# martice_relais.net
KiCad netlist of a schematic drawn in Altium Designer
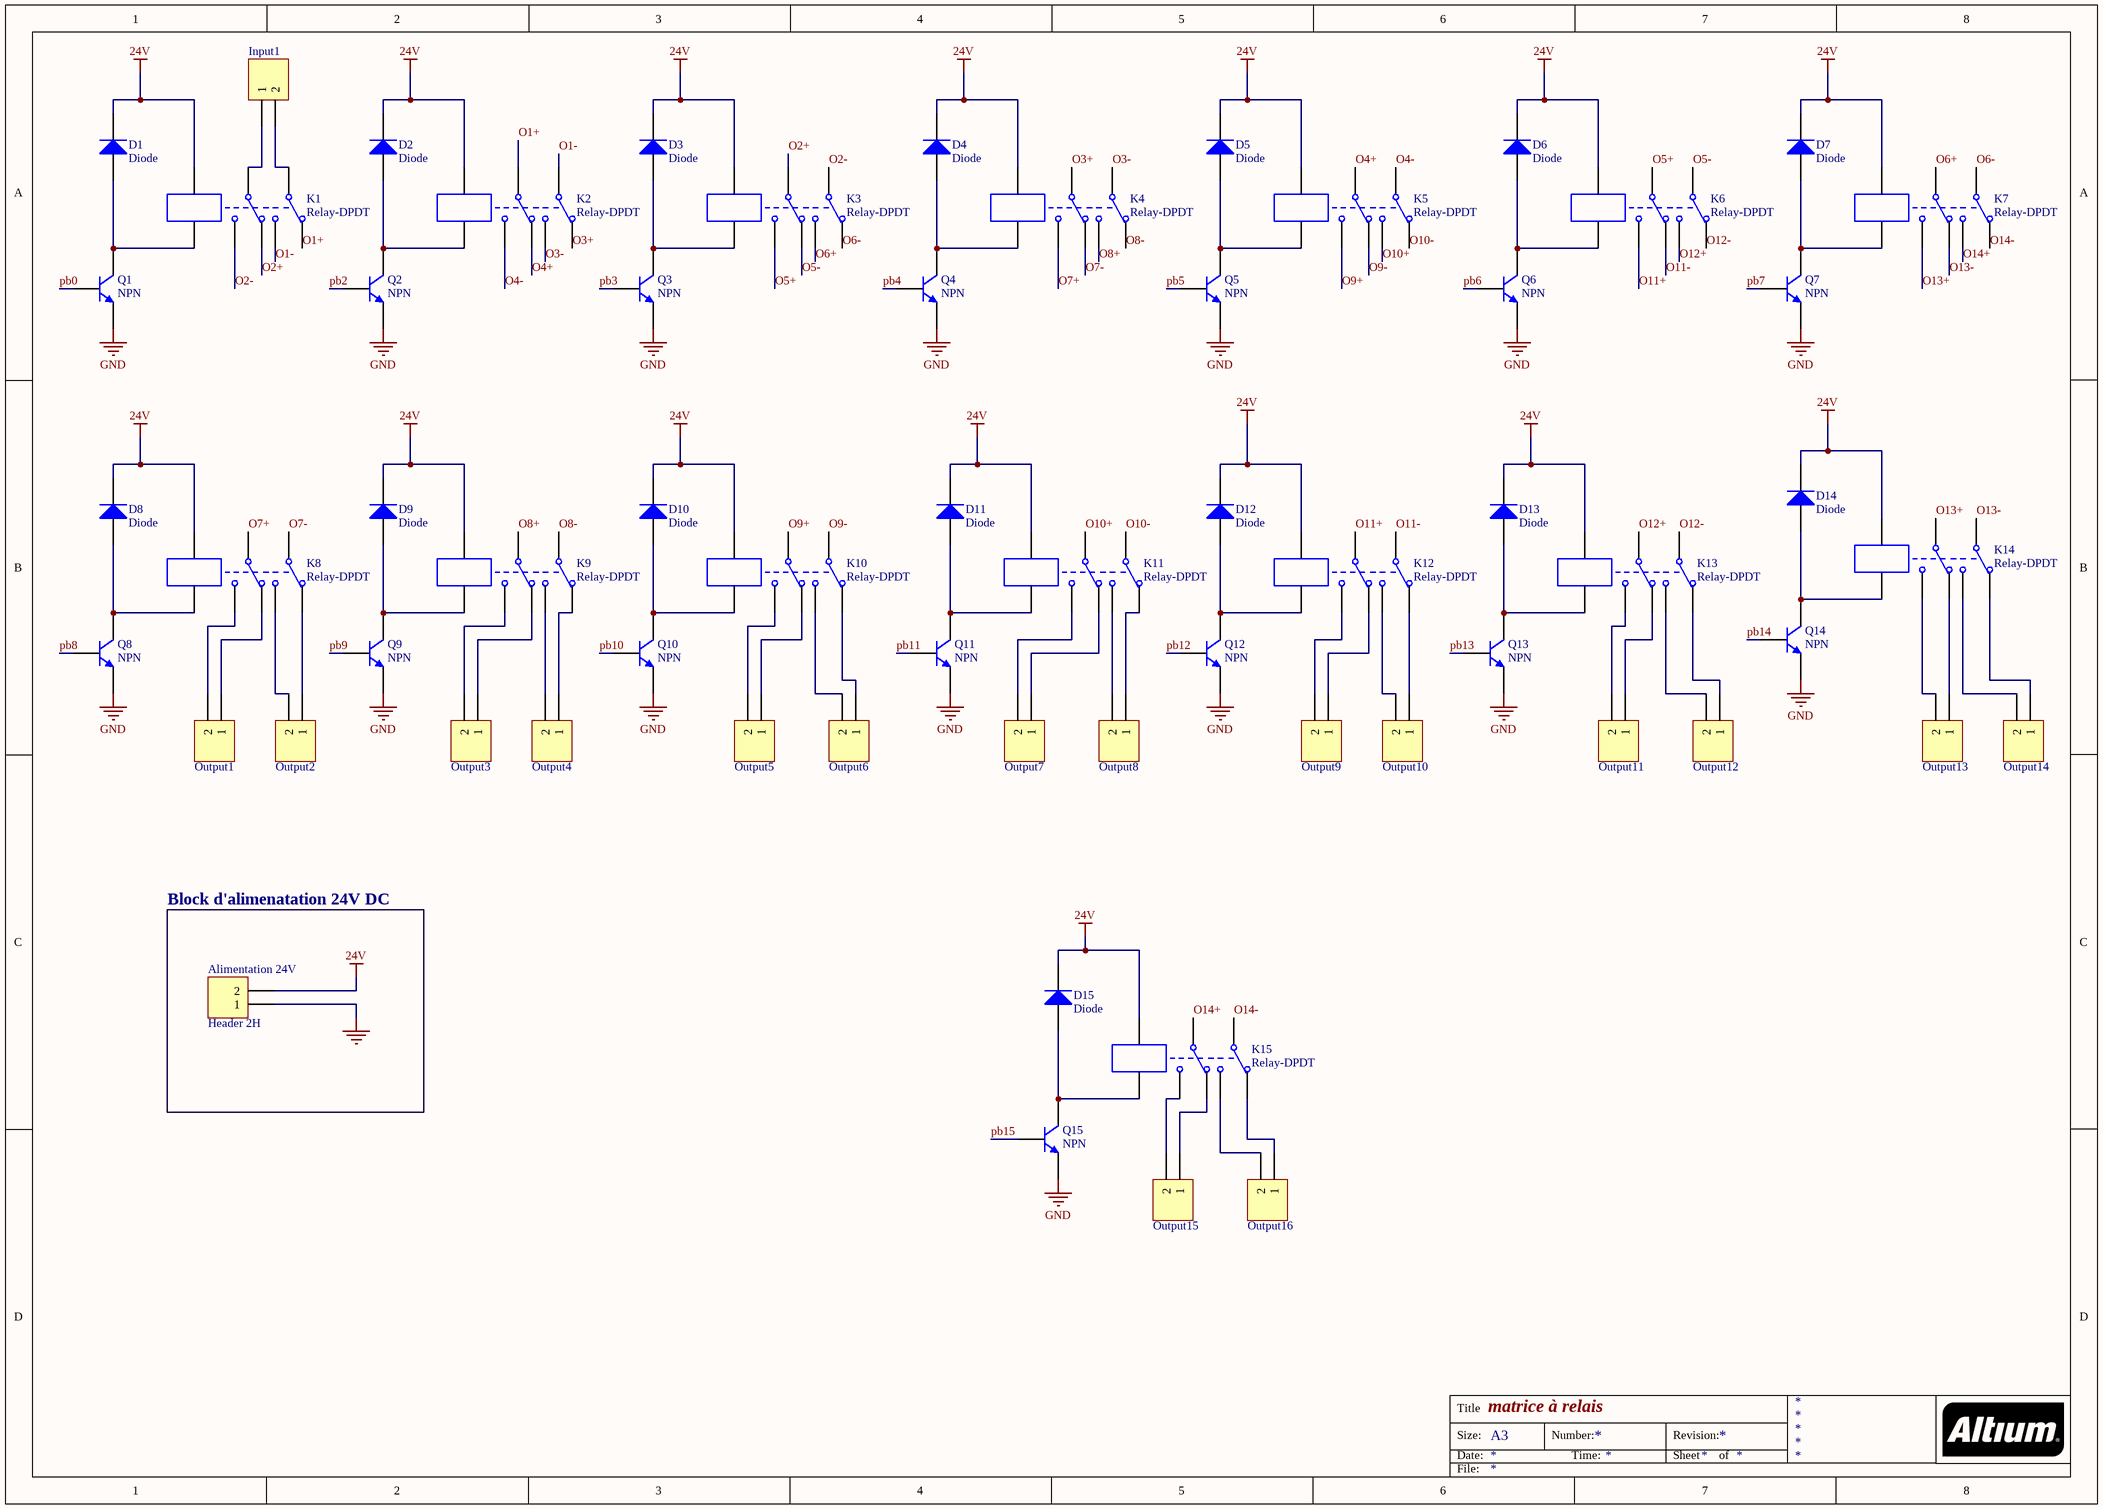
[diagram p0: martice_relais.SchDoc]

(export (version "E")
  (design (tool "Eeschema 10.0.6"))
  (components
    (comp (ref "Alimentation 24V")
      (value "Header 2H")
      (footprint "HDR1X2H")
      (description "Header, 2-Pin, Right Angle")
      (fields (field (name "PUBLISHER") "Altium Limited"))
      (libsource (lib "") (part "Header 2H_2"))
    )
    (comp (ref "D1")
      (value "Diode")
      (footprint "SMC")
      (description "Default Diode")
      (fields (field (name "PUBLISHER") "Altium Limited"))
      (libsource (lib "Miscellaneous Devices") (part "Diode"))
    )
    (comp (ref "D2")
      (value "Diode")
      (footprint "SMC")
      (description "Default Diode")
      (fields (field (name "PUBLISHER") "Altium Limited"))
      (libsource (lib "Miscellaneous Devices") (part "Diode"))
    )
    (comp (ref "D3")
      (value "Diode")
      (footprint "SMC")
      (description "Default Diode")
      (fields (field (name "PUBLISHER") "Altium Limited"))
      (libsource (lib "Miscellaneous Devices") (part "Diode"))
    )
    (comp (ref "D4")
      (value "Diode")
      (footprint "SMC")
      (description "Default Diode")
      (fields (field (name "PUBLISHER") "Altium Limited"))
      (libsource (lib "Miscellaneous Devices") (part "Diode"))
    )
    (comp (ref "D5")
      (value "Diode")
      (footprint "SMC")
      (description "Default Diode")
      (fields (field (name "PUBLISHER") "Altium Limited"))
      (libsource (lib "Miscellaneous Devices") (part "Diode"))
    )
    (comp (ref "D6")
      (value "Diode")
      (footprint "SMC")
      (description "Default Diode")
      (fields (field (name "PUBLISHER") "Altium Limited"))
      (libsource (lib "Miscellaneous Devices") (part "Diode"))
    )
    (comp (ref "D7")
      (value "Diode")
      (footprint "SMC")
      (description "Default Diode")
      (fields (field (name "PUBLISHER") "Altium Limited"))
      (libsource (lib "Miscellaneous Devices") (part "Diode"))
    )
    (comp (ref "D8")
      (value "Diode")
      (footprint "SMC")
      (description "Default Diode")
      (fields (field (name "PUBLISHER") "Altium Limited"))
      (libsource (lib "Miscellaneous Devices") (part "Diode"))
    )
    (comp (ref "D9")
      (value "Diode")
      (footprint "SMC")
      (description "Default Diode")
      (fields (field (name "PUBLISHER") "Altium Limited"))
      (libsource (lib "Miscellaneous Devices") (part "Diode"))
    )
    (comp (ref "D10")
      (value "Diode")
      (footprint "SMC")
      (description "Default Diode")
      (fields (field (name "PUBLISHER") "Altium Limited"))
      (libsource (lib "Miscellaneous Devices") (part "Diode"))
    )
    (comp (ref "D11")
      (value "Diode")
      (footprint "SMC")
      (description "Default Diode")
      (fields (field (name "PUBLISHER") "Altium Limited"))
      (libsource (lib "Miscellaneous Devices") (part "Diode"))
    )
    (comp (ref "D12")
      (value "Diode")
      (footprint "SMC")
      (description "Default Diode")
      (fields (field (name "PUBLISHER") "Altium Limited"))
      (libsource (lib "Miscellaneous Devices") (part "Diode"))
    )
    (comp (ref "D13")
      (value "Diode")
      (footprint "SMC")
      (description "Default Diode")
      (fields (field (name "PUBLISHER") "Altium Limited"))
      (libsource (lib "Miscellaneous Devices") (part "Diode"))
    )
    (comp (ref "D14")
      (value "Diode")
      (footprint "SMC")
      (description "Default Diode")
      (fields (field (name "PUBLISHER") "Altium Limited"))
      (libsource (lib "Miscellaneous Devices") (part "Diode"))
    )
    (comp (ref "D15")
      (value "Diode")
      (footprint "SMC")
      (description "Default Diode")
      (fields (field (name "PUBLISHER") "Altium Limited"))
      (libsource (lib "Miscellaneous Devices") (part "Diode"))
    )
    (comp (ref "Input1")
      (value "Header 2H")
      (footprint "HDR1X2H")
      (description "Header, 2-Pin, Right Angle")
      (fields (field (name "PUBLISHER") "Altium Limited"))
      (libsource (lib "") (part "Header 2H_1"))
    )
    (comp (ref "K1")
      (value "Relay-DPDT")
      (footprint "DIP-P8")
      (description "Dual-Pole Dual-Throw Relay")
      (fields (field (name "PUBLISHER") "Altium Limited"))
      (libsource (lib "Miscellaneous Devices") (part "Relay-DPDT"))
    )
    (comp (ref "K2")
      (value "Relay-DPDT")
      (footprint "DIP-P8")
      (description "Dual-Pole Dual-Throw Relay")
      (fields (field (name "PUBLISHER") "Altium Limited"))
      (libsource (lib "Miscellaneous Devices") (part "Relay-DPDT"))
    )
    (comp (ref "K3")
      (value "Relay-DPDT")
      (footprint "DIP-P8")
      (description "Dual-Pole Dual-Throw Relay")
      (fields (field (name "PUBLISHER") "Altium Limited"))
      (libsource (lib "Miscellaneous Devices") (part "Relay-DPDT"))
    )
    (comp (ref "K4")
      (value "Relay-DPDT")
      (footprint "DIP-P8")
      (description "Dual-Pole Dual-Throw Relay")
      (fields (field (name "PUBLISHER") "Altium Limited"))
      (libsource (lib "Miscellaneous Devices") (part "Relay-DPDT"))
    )
    (comp (ref "K5")
      (value "Relay-DPDT")
      (footprint "DIP-P8")
      (description "Dual-Pole Dual-Throw Relay")
      (fields (field (name "PUBLISHER") "Altium Limited"))
      (libsource (lib "Miscellaneous Devices") (part "Relay-DPDT"))
    )
    (comp (ref "K6")
      (value "Relay-DPDT")
      (footprint "DIP-P8")
      (description "Dual-Pole Dual-Throw Relay")
      (fields (field (name "PUBLISHER") "Altium Limited"))
      (libsource (lib "Miscellaneous Devices") (part "Relay-DPDT"))
    )
    (comp (ref "K7")
      (value "Relay-DPDT")
      (footprint "DIP-P8")
      (description "Dual-Pole Dual-Throw Relay")
      (fields (field (name "PUBLISHER") "Altium Limited"))
      (libsource (lib "Miscellaneous Devices") (part "Relay-DPDT"))
    )
    (comp (ref "K8")
      (value "Relay-DPDT")
      (footprint "DIP-P8")
      (description "Dual-Pole Dual-Throw Relay")
      (fields (field (name "PUBLISHER") "Altium Limited"))
      (libsource (lib "Miscellaneous Devices") (part "Relay-DPDT"))
    )
    (comp (ref "K9")
      (value "Relay-DPDT")
      (footprint "DIP-P8")
      (description "Dual-Pole Dual-Throw Relay")
      (fields (field (name "PUBLISHER") "Altium Limited"))
      (libsource (lib "Miscellaneous Devices") (part "Relay-DPDT"))
    )
    (comp (ref "K10")
      (value "Relay-DPDT")
      (footprint "DIP-P8")
      (description "Dual-Pole Dual-Throw Relay")
      (fields (field (name "PUBLISHER") "Altium Limited"))
      (libsource (lib "Miscellaneous Devices") (part "Relay-DPDT"))
    )
    (comp (ref "K11")
      (value "Relay-DPDT")
      (footprint "DIP-P8")
      (description "Dual-Pole Dual-Throw Relay")
      (fields (field (name "PUBLISHER") "Altium Limited"))
      (libsource (lib "Miscellaneous Devices") (part "Relay-DPDT"))
    )
    (comp (ref "K12")
      (value "Relay-DPDT")
      (footprint "DIP-P8")
      (description "Dual-Pole Dual-Throw Relay")
      (fields (field (name "PUBLISHER") "Altium Limited"))
      (libsource (lib "Miscellaneous Devices") (part "Relay-DPDT"))
    )
    (comp (ref "K13")
      (value "Relay-DPDT")
      (footprint "DIP-P8")
      (description "Dual-Pole Dual-Throw Relay")
      (fields (field (name "PUBLISHER") "Altium Limited"))
      (libsource (lib "Miscellaneous Devices") (part "Relay-DPDT"))
    )
    (comp (ref "K14")
      (value "Relay-DPDT")
      (footprint "DIP-P8")
      (description "Dual-Pole Dual-Throw Relay")
      (fields (field (name "PUBLISHER") "Altium Limited"))
      (libsource (lib "Miscellaneous Devices") (part "Relay-DPDT"))
    )
    (comp (ref "K15")
      (value "Relay-DPDT")
      (footprint "DIP-P8")
      (description "Dual-Pole Dual-Throw Relay")
      (fields (field (name "PUBLISHER") "Altium Limited"))
      (libsource (lib "Miscellaneous Devices") (part "Relay-DPDT"))
    )
    (comp (ref "Output1")
      (value "Header 2H")
      (footprint "HDR1X2H")
      (description "Header, 2-Pin, Right Angle")
      (fields (field (name "PUBLISHER") "Altium Limited"))
      (libsource (lib "Miscellaneous Connectors") (part "Header 2H"))
    )
    (comp (ref "Output2")
      (value "Header 2H")
      (footprint "HDR1X2H")
      (description "Header, 2-Pin, Right Angle")
      (fields (field (name "PUBLISHER") "Altium Limited"))
      (libsource (lib "Miscellaneous Connectors") (part "Header 2H"))
    )
    (comp (ref "Output3")
      (value "Header 2H")
      (footprint "HDR1X2H")
      (description "Header, 2-Pin, Right Angle")
      (fields (field (name "PUBLISHER") "Altium Limited"))
      (libsource (lib "Miscellaneous Connectors") (part "Header 2H"))
    )
    (comp (ref "Output4")
      (value "Header 2H")
      (footprint "HDR1X2H")
      (description "Header, 2-Pin, Right Angle")
      (fields (field (name "PUBLISHER") "Altium Limited"))
      (libsource (lib "Miscellaneous Connectors") (part "Header 2H"))
    )
    (comp (ref "Output5")
      (value "Header 2H")
      (footprint "HDR1X2H")
      (description "Header, 2-Pin, Right Angle")
      (fields (field (name "PUBLISHER") "Altium Limited"))
      (libsource (lib "Miscellaneous Connectors") (part "Header 2H"))
    )
    (comp (ref "Output6")
      (value "Header 2H")
      (footprint "HDR1X2H")
      (description "Header, 2-Pin, Right Angle")
      (fields (field (name "PUBLISHER") "Altium Limited"))
      (libsource (lib "Miscellaneous Connectors") (part "Header 2H"))
    )
    (comp (ref "Output7")
      (value "Header 2H")
      (footprint "HDR1X2H")
      (description "Header, 2-Pin, Right Angle")
      (fields (field (name "PUBLISHER") "Altium Limited"))
      (libsource (lib "Miscellaneous Connectors") (part "Header 2H"))
    )
    (comp (ref "Output8")
      (value "Header 2H")
      (footprint "HDR1X2H")
      (description "Header, 2-Pin, Right Angle")
      (fields (field (name "PUBLISHER") "Altium Limited"))
      (libsource (lib "Miscellaneous Connectors") (part "Header 2H"))
    )
    (comp (ref "Output9")
      (value "Header 2H")
      (footprint "HDR1X2H")
      (description "Header, 2-Pin, Right Angle")
      (fields (field (name "PUBLISHER") "Altium Limited"))
      (libsource (lib "Miscellaneous Connectors") (part "Header 2H"))
    )
    (comp (ref "Output10")
      (value "Header 2H")
      (footprint "HDR1X2H")
      (description "Header, 2-Pin, Right Angle")
      (fields (field (name "PUBLISHER") "Altium Limited"))
      (libsource (lib "Miscellaneous Connectors") (part "Header 2H"))
    )
    (comp (ref "Output11")
      (value "Header 2H")
      (footprint "HDR1X2H")
      (description "Header, 2-Pin, Right Angle")
      (fields (field (name "PUBLISHER") "Altium Limited"))
      (libsource (lib "Miscellaneous Connectors") (part "Header 2H"))
    )
    (comp (ref "Output12")
      (value "Header 2H")
      (footprint "HDR1X2H")
      (description "Header, 2-Pin, Right Angle")
      (fields (field (name "PUBLISHER") "Altium Limited"))
      (libsource (lib "Miscellaneous Connectors") (part "Header 2H"))
    )
    (comp (ref "Output13")
      (value "Header 2H")
      (footprint "HDR1X2H")
      (description "Header, 2-Pin, Right Angle")
      (fields (field (name "PUBLISHER") "Altium Limited"))
      (libsource (lib "Miscellaneous Connectors") (part "Header 2H"))
    )
    (comp (ref "Output14")
      (value "Header 2H")
      (footprint "HDR1X2H")
      (description "Header, 2-Pin, Right Angle")
      (fields (field (name "PUBLISHER") "Altium Limited"))
      (libsource (lib "Miscellaneous Connectors") (part "Header 2H"))
    )
    (comp (ref "Output15")
      (value "Header 2H")
      (footprint "HDR1X2H")
      (description "Header, 2-Pin, Right Angle")
      (fields (field (name "PUBLISHER") "Altium Limited"))
      (libsource (lib "Miscellaneous Connectors") (part "Header 2H"))
    )
    (comp (ref "Output16")
      (value "Header 2H")
      (footprint "HDR1X2H")
      (description "Header, 2-Pin, Right Angle")
      (fields (field (name "PUBLISHER") "Altium Limited"))
      (libsource (lib "Miscellaneous Connectors") (part "Header 2H"))
    )
    (comp (ref "Q1")
      (value "NPN")
      (footprint "TO-226-AA")
      (description "NPN Bipolar Transistor")
      (fields (field (name "PUBLISHER") "Altium Limited"))
      (libsource (lib "Miscellaneous Devices") (part "NPN"))
    )
    (comp (ref "Q2")
      (value "NPN")
      (footprint "TO-226-AA")
      (description "NPN Bipolar Transistor")
      (fields (field (name "PUBLISHER") "Altium Limited"))
      (libsource (lib "Miscellaneous Devices") (part "NPN"))
    )
    (comp (ref "Q3")
      (value "NPN")
      (footprint "TO-226-AA")
      (description "NPN Bipolar Transistor")
      (fields (field (name "PUBLISHER") "Altium Limited"))
      (libsource (lib "Miscellaneous Devices") (part "NPN"))
    )
    (comp (ref "Q4")
      (value "NPN")
      (footprint "TO-226-AA")
      (description "NPN Bipolar Transistor")
      (fields (field (name "PUBLISHER") "Altium Limited"))
      (libsource (lib "Miscellaneous Devices") (part "NPN"))
    )
    (comp (ref "Q5")
      (value "NPN")
      (footprint "TO-226-AA")
      (description "NPN Bipolar Transistor")
      (fields (field (name "PUBLISHER") "Altium Limited"))
      (libsource (lib "Miscellaneous Devices") (part "NPN"))
    )
    (comp (ref "Q6")
      (value "NPN")
      (footprint "TO-226-AA")
      (description "NPN Bipolar Transistor")
      (fields (field (name "PUBLISHER") "Altium Limited"))
      (libsource (lib "Miscellaneous Devices") (part "NPN"))
    )
    (comp (ref "Q7")
      (value "NPN")
      (footprint "TO-226-AA")
      (description "NPN Bipolar Transistor")
      (fields (field (name "PUBLISHER") "Altium Limited"))
      (libsource (lib "Miscellaneous Devices") (part "NPN"))
    )
    (comp (ref "Q8")
      (value "NPN")
      (footprint "TO-226-AA")
      (description "NPN Bipolar Transistor")
      (fields (field (name "PUBLISHER") "Altium Limited"))
      (libsource (lib "Miscellaneous Devices") (part "NPN"))
    )
    (comp (ref "Q9")
      (value "NPN")
      (footprint "TO-226-AA")
      (description "NPN Bipolar Transistor")
      (fields (field (name "PUBLISHER") "Altium Limited"))
      (libsource (lib "Miscellaneous Devices") (part "NPN"))
    )
    (comp (ref "Q10")
      (value "NPN")
      (footprint "TO-226-AA")
      (description "NPN Bipolar Transistor")
      (fields (field (name "PUBLISHER") "Altium Limited"))
      (libsource (lib "Miscellaneous Devices") (part "NPN"))
    )
    (comp (ref "Q11")
      (value "NPN")
      (footprint "TO-226-AA")
      (description "NPN Bipolar Transistor")
      (fields (field (name "PUBLISHER") "Altium Limited"))
      (libsource (lib "Miscellaneous Devices") (part "NPN"))
    )
    (comp (ref "Q12")
      (value "NPN")
      (footprint "TO-226-AA")
      (description "NPN Bipolar Transistor")
      (fields (field (name "PUBLISHER") "Altium Limited"))
      (libsource (lib "Miscellaneous Devices") (part "NPN"))
    )
    (comp (ref "Q13")
      (value "NPN")
      (footprint "TO-226-AA")
      (description "NPN Bipolar Transistor")
      (fields (field (name "PUBLISHER") "Altium Limited"))
      (libsource (lib "Miscellaneous Devices") (part "NPN"))
    )
    (comp (ref "Q14")
      (value "NPN")
      (footprint "TO-226-AA")
      (description "NPN Bipolar Transistor")
      (fields (field (name "PUBLISHER") "Altium Limited"))
      (libsource (lib "Miscellaneous Devices") (part "NPN"))
    )
    (comp (ref "Q15")
      (value "NPN")
      (footprint "TO-226-AA")
      (description "NPN Bipolar Transistor")
      (fields (field (name "PUBLISHER") "Altium Limited"))
      (libsource (lib "Miscellaneous Devices") (part "NPN"))
    )
  )
  (nets
    (net (code "1") (name "/O1+") (class "Default")
      (node (ref "K1") (pin "2") (pinfunction "2_2") (pintype "passive"))
      (node (ref "K2") (pin "4") (pinfunction "4_4") (pintype "passive"))
    )
    (net (code "2") (name "/O1-") (class "Default")
      (node (ref "K1") (pin "3") (pinfunction "3_3") (pintype "passive"))
      (node (ref "K2") (pin "1") (pinfunction "1_1") (pintype "passive"))
    )
    (net (code "3") (name "/O2+") (class "Default")
      (node (ref "K1") (pin "5") (pinfunction "5_5") (pintype "passive"))
      (node (ref "K3") (pin "4") (pinfunction "4_4") (pintype "passive"))
    )
    (net (code "4") (name "/O2-") (class "Default")
      (node (ref "K1") (pin "6") (pinfunction "6_6") (pintype "passive"))
      (node (ref "K3") (pin "1") (pinfunction "1_1") (pintype "passive"))
    )
    (net (code "5") (name "/O3+") (class "Default")
      (node (ref "K2") (pin "2") (pinfunction "2_2") (pintype "passive"))
      (node (ref "K4") (pin "4") (pinfunction "4_4") (pintype "passive"))
    )
    (net (code "6") (name "/O3-") (class "Default")
      (node (ref "K2") (pin "3") (pinfunction "3_3") (pintype "passive"))
      (node (ref "K4") (pin "1") (pinfunction "1_1") (pintype "passive"))
    )
    (net (code "7") (name "/O4+") (class "Default")
      (node (ref "K2") (pin "5") (pinfunction "5_5") (pintype "passive"))
      (node (ref "K5") (pin "4") (pinfunction "4_4") (pintype "passive"))
    )
    (net (code "8") (name "/O4-") (class "Default")
      (node (ref "K2") (pin "6") (pinfunction "6_6") (pintype "passive"))
      (node (ref "K5") (pin "1") (pinfunction "1_1") (pintype "passive"))
    )
    (net (code "9") (name "/O5+") (class "Default")
      (node (ref "K3") (pin "6") (pinfunction "6_6") (pintype "passive"))
      (node (ref "K6") (pin "4") (pinfunction "4_4") (pintype "passive"))
    )
    (net (code "10") (name "/O5-") (class "Default")
      (node (ref "K3") (pin "5") (pinfunction "5_5") (pintype "passive"))
      (node (ref "K6") (pin "1") (pinfunction "1_1") (pintype "passive"))
    )
    (net (code "11") (name "/O6+") (class "Default")
      (node (ref "K3") (pin "3") (pinfunction "3_3") (pintype "passive"))
      (node (ref "K7") (pin "4") (pinfunction "4_4") (pintype "passive"))
    )
    (net (code "12") (name "/O6-") (class "Default")
      (node (ref "K3") (pin "2") (pinfunction "2_2") (pintype "passive"))
      (node (ref "K7") (pin "1") (pinfunction "1_1") (pintype "passive"))
    )
    (net (code "13") (name "/O7+") (class "Default")
      (node (ref "K4") (pin "6") (pinfunction "6_6") (pintype "passive"))
      (node (ref "K8") (pin "4") (pinfunction "4_4") (pintype "passive"))
    )
    (net (code "14") (name "/O7-") (class "Default")
      (node (ref "K4") (pin "5") (pinfunction "5_5") (pintype "passive"))
      (node (ref "K8") (pin "1") (pinfunction "1_1") (pintype "passive"))
    )
    (net (code "15") (name "/O8+") (class "Default")
      (node (ref "K4") (pin "3") (pinfunction "3_3") (pintype "passive"))
      (node (ref "K9") (pin "4") (pinfunction "4_4") (pintype "passive"))
    )
    (net (code "16") (name "/O8-") (class "Default")
      (node (ref "K4") (pin "2") (pinfunction "2_2") (pintype "passive"))
      (node (ref "K9") (pin "1") (pinfunction "1_1") (pintype "passive"))
    )
    (net (code "17") (name "/O9+") (class "Default")
      (node (ref "K10") (pin "4") (pinfunction "4_4") (pintype "passive"))
      (node (ref "K5") (pin "6") (pinfunction "6_6") (pintype "passive"))
    )
    (net (code "18") (name "/O9-") (class "Default")
      (node (ref "K10") (pin "1") (pinfunction "1_1") (pintype "passive"))
      (node (ref "K5") (pin "5") (pinfunction "5_5") (pintype "passive"))
    )
    (net (code "19") (name "/O10+") (class "Default")
      (node (ref "K11") (pin "4") (pinfunction "4_4") (pintype "passive"))
      (node (ref "K5") (pin "3") (pinfunction "3_3") (pintype "passive"))
    )
    (net (code "20") (name "/O10-") (class "Default")
      (node (ref "K11") (pin "1") (pinfunction "1_1") (pintype "passive"))
      (node (ref "K5") (pin "2") (pinfunction "2_2") (pintype "passive"))
    )
    (net (code "21") (name "/O11+") (class "Default")
      (node (ref "K12") (pin "4") (pinfunction "4_4") (pintype "passive"))
      (node (ref "K6") (pin "6") (pinfunction "6_6") (pintype "passive"))
    )
    (net (code "22") (name "/O11-") (class "Default")
      (node (ref "K12") (pin "1") (pinfunction "1_1") (pintype "passive"))
      (node (ref "K6") (pin "5") (pinfunction "5_5") (pintype "passive"))
    )
    (net (code "23") (name "/O12+") (class "Default")
      (node (ref "K13") (pin "4") (pinfunction "4_4") (pintype "passive"))
      (node (ref "K6") (pin "3") (pinfunction "3_3") (pintype "passive"))
    )
    (net (code "24") (name "/O12-") (class "Default")
      (node (ref "K13") (pin "1") (pinfunction "1_1") (pintype "passive"))
      (node (ref "K6") (pin "2") (pinfunction "2_2") (pintype "passive"))
    )
    (net (code "25") (name "/O13+") (class "Default")
      (node (ref "K14") (pin "4") (pinfunction "4_4") (pintype "passive"))
      (node (ref "K7") (pin "6") (pinfunction "6_6") (pintype "passive"))
    )
    (net (code "26") (name "/O13-") (class "Default")
      (node (ref "K14") (pin "1") (pinfunction "1_1") (pintype "passive"))
      (node (ref "K7") (pin "5") (pinfunction "5_5") (pintype "passive"))
    )
    (net (code "27") (name "/O14+") (class "Default")
      (node (ref "K15") (pin "4") (pinfunction "4_4") (pintype "passive"))
      (node (ref "K7") (pin "3") (pinfunction "3_3") (pintype "passive"))
    )
    (net (code "28") (name "/O14-") (class "Default")
      (node (ref "K15") (pin "1") (pinfunction "1_1") (pintype "passive"))
      (node (ref "K7") (pin "2") (pinfunction "2_2") (pintype "passive"))
    )
    (net (code "29") (name "/pb0") (class "Default")
      (node (ref "Q1") (pin "2") (pinfunction "B_2") (pintype "passive"))
    )
    (net (code "30") (name "/pb2") (class "Default")
      (node (ref "Q2") (pin "2") (pinfunction "B_2") (pintype "passive"))
    )
    (net (code "31") (name "/pb3") (class "Default")
      (node (ref "Q3") (pin "2") (pinfunction "B_2") (pintype "passive"))
    )
    (net (code "32") (name "/pb4") (class "Default")
      (node (ref "Q4") (pin "2") (pinfunction "B_2") (pintype "passive"))
    )
    (net (code "33") (name "/pb5") (class "Default")
      (node (ref "Q5") (pin "2") (pinfunction "B_2") (pintype "passive"))
    )
    (net (code "34") (name "/pb6") (class "Default")
      (node (ref "Q6") (pin "2") (pinfunction "B_2") (pintype "passive"))
    )
    (net (code "35") (name "/pb7") (class "Default")
      (node (ref "Q7") (pin "2") (pinfunction "B_2") (pintype "passive"))
    )
    (net (code "36") (name "/pb8") (class "Default")
      (node (ref "Q8") (pin "2") (pinfunction "B_2") (pintype "passive"))
    )
    (net (code "37") (name "/pb9") (class "Default")
      (node (ref "Q9") (pin "2") (pinfunction "B_2") (pintype "passive"))
    )
    (net (code "38") (name "/pb10") (class "Default")
      (node (ref "Q10") (pin "2") (pinfunction "B_2") (pintype "passive"))
    )
    (net (code "39") (name "/pb11") (class "Default")
      (node (ref "Q11") (pin "2") (pinfunction "B_2") (pintype "passive"))
    )
    (net (code "40") (name "/pb12") (class "Default")
      (node (ref "Q12") (pin "2") (pinfunction "B_2") (pintype "passive"))
    )
    (net (code "41") (name "/pb13") (class "Default")
      (node (ref "Q13") (pin "2") (pinfunction "B_2") (pintype "passive"))
    )
    (net (code "42") (name "/pb14") (class "Default")
      (node (ref "Q14") (pin "2") (pinfunction "B_2") (pintype "passive"))
    )
    (net (code "43") (name "/pb15") (class "Default")
      (node (ref "Q15") (pin "2") (pinfunction "B_2") (pintype "passive"))
    )
    (net (code "44") (name "24V") (class "Default")
      (node (ref "Alimentation 24V") (pin "2") (pinfunction "2_2") (pintype "passive"))
      (node (ref "D1") (pin "2") (pinfunction "K_2") (pintype "passive"))
      (node (ref "D10") (pin "2") (pinfunction "K_2") (pintype "passive"))
      (node (ref "D11") (pin "2") (pinfunction "K_2") (pintype "passive"))
      (node (ref "D12") (pin "2") (pinfunction "K_2") (pintype "passive"))
      (node (ref "D13") (pin "2") (pinfunction "K_2") (pintype "passive"))
      (node (ref "D14") (pin "2") (pinfunction "K_2") (pintype "passive"))
      (node (ref "D15") (pin "2") (pinfunction "K_2") (pintype "passive"))
      (node (ref "D2") (pin "2") (pinfunction "K_2") (pintype "passive"))
      (node (ref "D3") (pin "2") (pinfunction "K_2") (pintype "passive"))
      (node (ref "D4") (pin "2") (pinfunction "K_2") (pintype "passive"))
      (node (ref "D5") (pin "2") (pinfunction "K_2") (pintype "passive"))
      (node (ref "D6") (pin "2") (pinfunction "K_2") (pintype "passive"))
      (node (ref "D7") (pin "2") (pinfunction "K_2") (pintype "passive"))
      (node (ref "D8") (pin "2") (pinfunction "K_2") (pintype "passive"))
      (node (ref "D9") (pin "2") (pinfunction "K_2") (pintype "passive"))
      (node (ref "K1") (pin "7") (pinfunction "7_7") (pintype "passive"))
      (node (ref "K10") (pin "7") (pinfunction "7_7") (pintype "passive"))
      (node (ref "K11") (pin "7") (pinfunction "7_7") (pintype "passive"))
      (node (ref "K12") (pin "7") (pinfunction "7_7") (pintype "passive"))
      (node (ref "K13") (pin "7") (pinfunction "7_7") (pintype "passive"))
      (node (ref "K14") (pin "7") (pinfunction "7_7") (pintype "passive"))
      (node (ref "K15") (pin "7") (pinfunction "7_7") (pintype "passive"))
      (node (ref "K2") (pin "7") (pinfunction "7_7") (pintype "passive"))
      (node (ref "K3") (pin "7") (pinfunction "7_7") (pintype "passive"))
      (node (ref "K4") (pin "7") (pinfunction "7_7") (pintype "passive"))
      (node (ref "K5") (pin "7") (pinfunction "7_7") (pintype "passive"))
      (node (ref "K6") (pin "7") (pinfunction "7_7") (pintype "passive"))
      (node (ref "K7") (pin "7") (pinfunction "7_7") (pintype "passive"))
      (node (ref "K8") (pin "7") (pinfunction "7_7") (pintype "passive"))
      (node (ref "K9") (pin "7") (pinfunction "7_7") (pintype "passive"))
    )
    (net (code "45") (name "<NO NET>") (class "Default")
      (node (ref "Alimentation 24V") (pin "1") (pinfunction "1_1") (pintype "passive"))
    )
    (net (code "46") (name "GND") (class "Default")
      (node (ref "Q1") (pin "3") (pinfunction "E_3") (pintype "passive"))
      (node (ref "Q10") (pin "3") (pinfunction "E_3") (pintype "passive"))
      (node (ref "Q11") (pin "3") (pinfunction "E_3") (pintype "passive"))
      (node (ref "Q12") (pin "3") (pinfunction "E_3") (pintype "passive"))
      (node (ref "Q13") (pin "3") (pinfunction "E_3") (pintype "passive"))
      (node (ref "Q14") (pin "3") (pinfunction "E_3") (pintype "passive"))
      (node (ref "Q15") (pin "3") (pinfunction "E_3") (pintype "passive"))
      (node (ref "Q2") (pin "3") (pinfunction "E_3") (pintype "passive"))
      (node (ref "Q3") (pin "3") (pinfunction "E_3") (pintype "passive"))
      (node (ref "Q4") (pin "3") (pinfunction "E_3") (pintype "passive"))
      (node (ref "Q5") (pin "3") (pinfunction "E_3") (pintype "passive"))
      (node (ref "Q6") (pin "3") (pinfunction "E_3") (pintype "passive"))
      (node (ref "Q7") (pin "3") (pinfunction "E_3") (pintype "passive"))
      (node (ref "Q8") (pin "3") (pinfunction "E_3") (pintype "passive"))
      (node (ref "Q9") (pin "3") (pinfunction "E_3") (pintype "passive"))
    )
    (net (code "47") (name "Net-(D1-A)") (class "Default")
      (node (ref "D1") (pin "1") (pinfunction "A_1") (pintype "passive"))
      (node (ref "K1") (pin "8") (pinfunction "8_8") (pintype "passive"))
      (node (ref "Q1") (pin "1") (pinfunction "C_1") (pintype "passive"))
    )
    (net (code "48") (name "Net-(D2-A)") (class "Default")
      (node (ref "D2") (pin "1") (pinfunction "A_1") (pintype "passive"))
      (node (ref "K2") (pin "8") (pinfunction "8_8") (pintype "passive"))
      (node (ref "Q2") (pin "1") (pinfunction "C_1") (pintype "passive"))
    )
    (net (code "49") (name "Net-(D3-A)") (class "Default")
      (node (ref "D3") (pin "1") (pinfunction "A_1") (pintype "passive"))
      (node (ref "K3") (pin "8") (pinfunction "8_8") (pintype "passive"))
      (node (ref "Q3") (pin "1") (pinfunction "C_1") (pintype "passive"))
    )
    (net (code "50") (name "Net-(D4-A)") (class "Default")
      (node (ref "D4") (pin "1") (pinfunction "A_1") (pintype "passive"))
      (node (ref "K4") (pin "8") (pinfunction "8_8") (pintype "passive"))
      (node (ref "Q4") (pin "1") (pinfunction "C_1") (pintype "passive"))
    )
    (net (code "51") (name "Net-(D5-A)") (class "Default")
      (node (ref "D5") (pin "1") (pinfunction "A_1") (pintype "passive"))
      (node (ref "K5") (pin "8") (pinfunction "8_8") (pintype "passive"))
      (node (ref "Q5") (pin "1") (pinfunction "C_1") (pintype "passive"))
    )
    (net (code "52") (name "Net-(D6-A)") (class "Default")
      (node (ref "D6") (pin "1") (pinfunction "A_1") (pintype "passive"))
      (node (ref "K6") (pin "8") (pinfunction "8_8") (pintype "passive"))
      (node (ref "Q6") (pin "1") (pinfunction "C_1") (pintype "passive"))
    )
    (net (code "53") (name "Net-(D7-A)") (class "Default")
      (node (ref "D7") (pin "1") (pinfunction "A_1") (pintype "passive"))
      (node (ref "K7") (pin "8") (pinfunction "8_8") (pintype "passive"))
      (node (ref "Q7") (pin "1") (pinfunction "C_1") (pintype "passive"))
    )
    (net (code "54") (name "Net-(D8-A)") (class "Default")
      (node (ref "D8") (pin "1") (pinfunction "A_1") (pintype "passive"))
      (node (ref "K8") (pin "8") (pinfunction "8_8") (pintype "passive"))
      (node (ref "Q8") (pin "1") (pinfunction "C_1") (pintype "passive"))
    )
    (net (code "55") (name "Net-(D9-A)") (class "Default")
      (node (ref "D9") (pin "1") (pinfunction "A_1") (pintype "passive"))
      (node (ref "K9") (pin "8") (pinfunction "8_8") (pintype "passive"))
      (node (ref "Q9") (pin "1") (pinfunction "C_1") (pintype "passive"))
    )
    (net (code "56") (name "Net-(D10-A)") (class "Default")
      (node (ref "D10") (pin "1") (pinfunction "A_1") (pintype "passive"))
      (node (ref "K10") (pin "8") (pinfunction "8_8") (pintype "passive"))
      (node (ref "Q10") (pin "1") (pinfunction "C_1") (pintype "passive"))
    )
    (net (code "57") (name "Net-(D11-A)") (class "Default")
      (node (ref "D11") (pin "1") (pinfunction "A_1") (pintype "passive"))
      (node (ref "K11") (pin "8") (pinfunction "8_8") (pintype "passive"))
      (node (ref "Q11") (pin "1") (pinfunction "C_1") (pintype "passive"))
    )
    (net (code "58") (name "Net-(D12-A)") (class "Default")
      (node (ref "D12") (pin "1") (pinfunction "A_1") (pintype "passive"))
      (node (ref "K12") (pin "8") (pinfunction "8_8") (pintype "passive"))
      (node (ref "Q12") (pin "1") (pinfunction "C_1") (pintype "passive"))
    )
    (net (code "59") (name "Net-(D13-A)") (class "Default")
      (node (ref "D13") (pin "1") (pinfunction "A_1") (pintype "passive"))
      (node (ref "K13") (pin "8") (pinfunction "8_8") (pintype "passive"))
      (node (ref "Q13") (pin "1") (pinfunction "C_1") (pintype "passive"))
    )
    (net (code "60") (name "Net-(D14-A)") (class "Default")
      (node (ref "D14") (pin "1") (pinfunction "A_1") (pintype "passive"))
      (node (ref "K14") (pin "8") (pinfunction "8_8") (pintype "passive"))
      (node (ref "Q14") (pin "1") (pinfunction "C_1") (pintype "passive"))
    )
    (net (code "61") (name "Net-(D15-A)") (class "Default")
      (node (ref "D15") (pin "1") (pinfunction "A_1") (pintype "passive"))
      (node (ref "K15") (pin "8") (pinfunction "8_8") (pintype "passive"))
      (node (ref "Q15") (pin "1") (pinfunction "C_1") (pintype "passive"))
    )
    (net (code "62") (name "Net-(Input1-Pad1)") (class "Default")
      (node (ref "Input1") (pin "1") (pinfunction "1_1") (pintype "passive"))
      (node (ref "K1") (pin "4") (pinfunction "4_4") (pintype "passive"))
    )
    (net (code "63") (name "Net-(Input1-Pad2)") (class "Default")
      (node (ref "Input1") (pin "2") (pinfunction "2_2") (pintype "passive"))
      (node (ref "K1") (pin "1") (pinfunction "1_1") (pintype "passive"))
    )
    (net (code "64") (name "Net-(K8-Pad2)") (class "Default")
      (node (ref "K8") (pin "2") (pinfunction "2_2") (pintype "passive"))
      (node (ref "Output2") (pin "1") (pinfunction "1_1") (pintype "passive"))
    )
    (net (code "65") (name "Net-(K8-Pad3)") (class "Default")
      (node (ref "K8") (pin "3") (pinfunction "3_3") (pintype "passive"))
      (node (ref "Output2") (pin "2") (pinfunction "2_2") (pintype "passive"))
    )
    (net (code "66") (name "Net-(K8-Pad5)") (class "Default")
      (node (ref "K8") (pin "5") (pinfunction "5_5") (pintype "passive"))
      (node (ref "Output1") (pin "1") (pinfunction "1_1") (pintype "passive"))
    )
    (net (code "67") (name "Net-(K8-Pad6)") (class "Default")
      (node (ref "K8") (pin "6") (pinfunction "6_6") (pintype "passive"))
      (node (ref "Output1") (pin "2") (pinfunction "2_2") (pintype "passive"))
    )
    (net (code "68") (name "Net-(K9-Pad2)") (class "Default")
      (node (ref "K9") (pin "2") (pinfunction "2_2") (pintype "passive"))
      (node (ref "Output4") (pin "1") (pinfunction "1_1") (pintype "passive"))
    )
    (net (code "69") (name "Net-(K9-Pad3)") (class "Default")
      (node (ref "K9") (pin "3") (pinfunction "3_3") (pintype "passive"))
      (node (ref "Output4") (pin "2") (pinfunction "2_2") (pintype "passive"))
    )
    (net (code "70") (name "Net-(K9-Pad5)") (class "Default")
      (node (ref "K9") (pin "5") (pinfunction "5_5") (pintype "passive"))
      (node (ref "Output3") (pin "1") (pinfunction "1_1") (pintype "passive"))
    )
    (net (code "71") (name "Net-(K9-Pad6)") (class "Default")
      (node (ref "K9") (pin "6") (pinfunction "6_6") (pintype "passive"))
      (node (ref "Output3") (pin "2") (pinfunction "2_2") (pintype "passive"))
    )
    (net (code "72") (name "Net-(K10-Pad2)") (class "Default")
      (node (ref "K10") (pin "2") (pinfunction "2_2") (pintype "passive"))
      (node (ref "Output6") (pin "1") (pinfunction "1_1") (pintype "passive"))
    )
    (net (code "73") (name "Net-(K10-Pad3)") (class "Default")
      (node (ref "K10") (pin "3") (pinfunction "3_3") (pintype "passive"))
      (node (ref "Output6") (pin "2") (pinfunction "2_2") (pintype "passive"))
    )
    (net (code "74") (name "Net-(K10-Pad5)") (class "Default")
      (node (ref "K10") (pin "5") (pinfunction "5_5") (pintype "passive"))
      (node (ref "Output5") (pin "1") (pinfunction "1_1") (pintype "passive"))
    )
    (net (code "75") (name "Net-(K10-Pad6)") (class "Default")
      (node (ref "K10") (pin "6") (pinfunction "6_6") (pintype "passive"))
      (node (ref "Output5") (pin "2") (pinfunction "2_2") (pintype "passive"))
    )
    (net (code "76") (name "Net-(K11-Pad2)") (class "Default")
      (node (ref "K11") (pin "2") (pinfunction "2_2") (pintype "passive"))
      (node (ref "Output8") (pin "1") (pinfunction "1_1") (pintype "passive"))
    )
    (net (code "77") (name "Net-(K11-Pad3)") (class "Default")
      (node (ref "K11") (pin "3") (pinfunction "3_3") (pintype "passive"))
      (node (ref "Output8") (pin "2") (pinfunction "2_2") (pintype "passive"))
    )
    (net (code "78") (name "Net-(K11-Pad5)") (class "Default")
      (node (ref "K11") (pin "5") (pinfunction "5_5") (pintype "passive"))
      (node (ref "Output7") (pin "1") (pinfunction "1_1") (pintype "passive"))
    )
    (net (code "79") (name "Net-(K11-Pad6)") (class "Default")
      (node (ref "K11") (pin "6") (pinfunction "6_6") (pintype "passive"))
      (node (ref "Output7") (pin "2") (pinfunction "2_2") (pintype "passive"))
    )
    (net (code "80") (name "Net-(K12-Pad2)") (class "Default")
      (node (ref "K12") (pin "2") (pinfunction "2_2") (pintype "passive"))
      (node (ref "Output10") (pin "1") (pinfunction "1_1") (pintype "passive"))
    )
    (net (code "81") (name "Net-(K12-Pad3)") (class "Default")
      (node (ref "K12") (pin "3") (pinfunction "3_3") (pintype "passive"))
      (node (ref "Output10") (pin "2") (pinfunction "2_2") (pintype "passive"))
    )
    (net (code "82") (name "Net-(K12-Pad5)") (class "Default")
      (node (ref "K12") (pin "5") (pinfunction "5_5") (pintype "passive"))
      (node (ref "Output9") (pin "1") (pinfunction "1_1") (pintype "passive"))
    )
    (net (code "83") (name "Net-(K12-Pad6)") (class "Default")
      (node (ref "K12") (pin "6") (pinfunction "6_6") (pintype "passive"))
      (node (ref "Output9") (pin "2") (pinfunction "2_2") (pintype "passive"))
    )
    (net (code "84") (name "Net-(K13-Pad2)") (class "Default")
      (node (ref "K13") (pin "2") (pinfunction "2_2") (pintype "passive"))
      (node (ref "Output12") (pin "1") (pinfunction "1_1") (pintype "passive"))
    )
    (net (code "85") (name "Net-(K13-Pad3)") (class "Default")
      (node (ref "K13") (pin "3") (pinfunction "3_3") (pintype "passive"))
      (node (ref "Output12") (pin "2") (pinfunction "2_2") (pintype "passive"))
    )
    (net (code "86") (name "Net-(K13-Pad5)") (class "Default")
      (node (ref "K13") (pin "5") (pinfunction "5_5") (pintype "passive"))
      (node (ref "Output11") (pin "1") (pinfunction "1_1") (pintype "passive"))
    )
    (net (code "87") (name "Net-(K13-Pad6)") (class "Default")
      (node (ref "K13") (pin "6") (pinfunction "6_6") (pintype "passive"))
      (node (ref "Output11") (pin "2") (pinfunction "2_2") (pintype "passive"))
    )
    (net (code "88") (name "Net-(K14-Pad2)") (class "Default")
      (node (ref "K14") (pin "2") (pinfunction "2_2") (pintype "passive"))
      (node (ref "Output14") (pin "1") (pinfunction "1_1") (pintype "passive"))
    )
    (net (code "89") (name "Net-(K14-Pad3)") (class "Default")
      (node (ref "K14") (pin "3") (pinfunction "3_3") (pintype "passive"))
      (node (ref "Output14") (pin "2") (pinfunction "2_2") (pintype "passive"))
    )
    (net (code "90") (name "Net-(K14-Pad5)") (class "Default")
      (node (ref "K14") (pin "5") (pinfunction "5_5") (pintype "passive"))
      (node (ref "Output13") (pin "1") (pinfunction "1_1") (pintype "passive"))
    )
    (net (code "91") (name "Net-(K14-Pad6)") (class "Default")
      (node (ref "K14") (pin "6") (pinfunction "6_6") (pintype "passive"))
      (node (ref "Output13") (pin "2") (pinfunction "2_2") (pintype "passive"))
    )
    (net (code "92") (name "Net-(K15-Pad2)") (class "Default")
      (node (ref "K15") (pin "2") (pinfunction "2_2") (pintype "passive"))
      (node (ref "Output16") (pin "1") (pinfunction "1_1") (pintype "passive"))
    )
    (net (code "93") (name "Net-(K15-Pad3)") (class "Default")
      (node (ref "K15") (pin "3") (pinfunction "3_3") (pintype "passive"))
      (node (ref "Output16") (pin "2") (pinfunction "2_2") (pintype "passive"))
    )
    (net (code "94") (name "Net-(K15-Pad5)") (class "Default")
      (node (ref "K15") (pin "5") (pinfunction "5_5") (pintype "passive"))
      (node (ref "Output15") (pin "1") (pinfunction "1_1") (pintype "passive"))
    )
    (net (code "95") (name "Net-(K15-Pad6)") (class "Default")
      (node (ref "K15") (pin "6") (pinfunction "6_6") (pintype "passive"))
      (node (ref "Output15") (pin "2") (pinfunction "2_2") (pintype "passive"))
    )
  )
)
